# PWR.net
KiCad netlist of a schematic drawn in Altium Designer
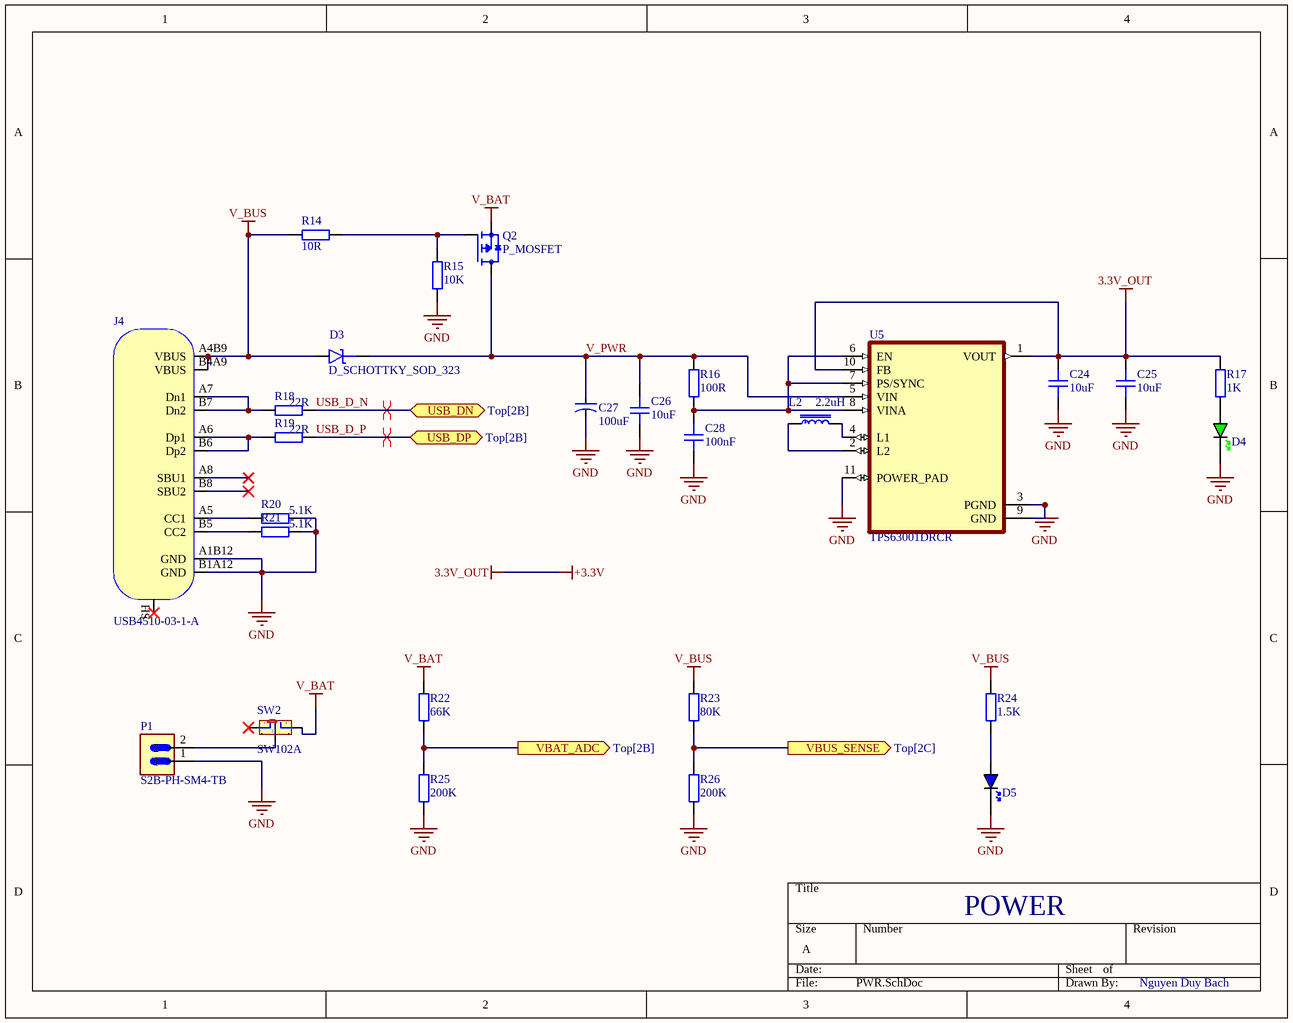
[diagram p0: PWR.SchDoc]

(export (version "E")
  (design (tool "Eeschema 10.0.6"))
  (components
    (comp (ref "C24")
      (value "10uF")
      (footprint "CAP_1206")
      (description "Capacitor SMD 1206")
      (libsource (lib "Project") (part "CAP_1206"))
    )
    (comp (ref "C25")
      (value "10uF")
      (footprint "CAP_1206")
      (description "Capacitor SMD 1206")
      (libsource (lib "Project") (part "CAP_1206"))
    )
    (comp (ref "C26")
      (value "10uF")
      (footprint "CAP_1206")
      (description "Capacitor SMD 1206")
      (libsource (lib "Project") (part "CAP_1206"))
    )
    (comp (ref "C27")
      (value "100uF")
      (footprint "CAP-ALU-SMD-6.3x7.7x2.2")
      (description "Polarized Capacitor (Axial)")
      (fields (field (name "PUBLISHER") "Altium Limited"))
      (libsource (lib "LIBRARY") (part "CN-ALU-SMD"))
    )
    (comp (ref "C28")
      (value "100nF")
      (footprint "CAP_0603")
      (description "Capacitor SMD 0603")
      (libsource (lib "Project") (part "CAP_0603"))
    )
    (comp (ref "D3")
      (value "D_SCHOTTKY_SOD_323")
      (footprint "SOD-323")
      (description "Diode Schottky SMD SOD-323")
      (libsource (lib "Schematic-Lib-PhilsLab") (part "D_SCHOTTKY_SOD_323"))
    )
    (comp (ref "D4")
      (value "GREEN")
      (footprint "LED_0805_GREEN")
      (description "LED 0805 GREEN SMD")
      (libsource (lib "Project") (part "LED_0805_GREEN"))
    )
    (comp (ref "D5")
      (value "BLUE")
      (footprint "LED_0805_BLUE")
      (description "LED 0805 BLUE SMD")
      (libsource (lib "Project") (part "LED_0805_BLUE"))
    )
    (comp (ref "J4")
      (value "USB4510-03-1-A")
      (footprint "USB4510-03-1-A")
      (description "USB Connector Type C SMT Mid-Mount 16 Pin")
      (fields (field (name "MANUFACTURER") "GCT"))
      (libsource (lib "Schematic-Lib-PhilsLab") (part "USB4510-03-1-A"))
    )
    (comp (ref "L2")
      (value "2.2uH")
      (footprint "INDC6060X300")
      (description "SMD Inductor 10uH-20%-5A")
      (fields (field (name "MF") "Codaca") (field (name "MP") "CSAB0630-100M"))
      (libsource (lib "Project") (part "CSAB0630-100M"))
    )
    (comp (ref "P1")
      (value "S2B-PH-SM4-TB")
      (footprint "JST_S2B-PH-SM4-TB")
      (description "Connector Header Surface Mount, Right Angle 2 position 0.079 (2.00mm)")
      (fields (field (name "MF") "JST Sales"))
      (libsource (lib "Project") (part "S2B-PH-SM4-TB"))
    )
    (comp (ref "Q2")
      (value "P_MOSFET")
      (footprint "P_MOSFET_SOT23")
      (description "MOSFET, SOT-23, P, -30V, -4A, 0.065â„¦, 150Â°C")
      (fields (field (name "MF") "Diotec Semiconductor") (field (name "MP") "MMFTP3401"))
      (libsource (lib "Project") (part "P_MOSFET"))
    )
    (comp (ref "R14")
      (value "10R")
      (footprint "RES_0603")
      (description "Resistor SMD 0603")
      (libsource (lib "Project") (part "RES_0603"))
    )
    (comp (ref "R15")
      (value "10K")
      (footprint "RES_0603")
      (description "Resistor SMD 0603")
      (libsource (lib "Project") (part "RES_0603"))
    )
    (comp (ref "R16")
      (value "100R")
      (footprint "RES_1206")
      (description "Resistor SMD 1206")
      (libsource (lib "Project") (part "RES_1206"))
    )
    (comp (ref "R17")
      (value "1K")
      (footprint "RES_0805")
      (description "Resistor SMD 0805")
      (libsource (lib "Project") (part "RES_0805"))
    )
    (comp (ref "R18")
      (value "22R")
      (footprint "RES_0603")
      (description "Resistor SMD 0603")
      (libsource (lib "Project") (part "RES_0603"))
    )
    (comp (ref "R19")
      (value "22R")
      (footprint "RES_0603")
      (description "Resistor SMD 0603")
      (libsource (lib "Project") (part "RES_0603"))
    )
    (comp (ref "R20")
      (value "5.1K")
      (footprint "RES_0603")
      (description "Resistor SMD 0603")
      (libsource (lib "Project") (part "RES_0603"))
    )
    (comp (ref "R21")
      (value "5.1K")
      (footprint "RES_0603")
      (description "Resistor SMD 0603")
      (libsource (lib "Project") (part "RES_0603"))
    )
    (comp (ref "R22")
      (value "66K")
      (footprint "RES_0603")
      (description "Resistor SMD 0603")
      (libsource (lib "Project") (part "RES_0603"))
    )
    (comp (ref "R23")
      (value "80K")
      (footprint "RES_0603")
      (description "Resistor SMD 0603")
      (libsource (lib "Project") (part "RES_0603"))
    )
    (comp (ref "R24")
      (value "1.5K")
      (footprint "RES_0805")
      (description "Resistor SMD 0805")
      (libsource (lib "Project") (part "RES_0805"))
    )
    (comp (ref "R25")
      (value "200K")
      (footprint "RES_0603")
      (description "Resistor SMD 0603")
      (libsource (lib "Project") (part "RES_0603"))
    )
    (comp (ref "R26")
      (value "200K")
      (footprint "RES_0603")
      (description "Resistor SMD 0603")
      (libsource (lib "Project") (part "RES_0603"))
    )
    (comp (ref "SW2")
      (value "SW102A")
      (footprint "SW102")
      (description "Switch 102 on Broad")
      (libsource (lib "syhaunguyen") (part "SW102A"))
    )
    (comp (ref "U5")
      (value "TPS63001DRCR")
      (footprint "VREG_V62/16624-01YE")
      (description "96% Buck-Boost Converter with 1.7A Current Switches, 3.3V fixed Output voltage in 3x3 QFN")
      (fields (field (name "MF") "Texas Instruments"))
      (libsource (lib "Project") (part "TPS63001DRCR"))
    )
  )
  (nets
    (net (code "1") (name "+3.3V") (class "Default")
      (node (ref "C24") (pin "2") (pinfunction "2_2") (pintype "passive"))
      (node (ref "C25") (pin "2") (pinfunction "2_2") (pintype "passive"))
      (node (ref "R17") (pin "2") (pinfunction "2_2") (pintype "passive"))
      (node (ref "U5") (pin "1") (pinfunction "VOUT_1") (pintype "output"))
      (node (ref "U5") (pin "10") (pinfunction "FB_10") (pintype "input"))
    )
    (net (code "2") (name "/USB_D_N") (class "Default")
      (node (ref "R18") (pin "1") (pinfunction "1_1") (pintype "passive"))
    )
    (net (code "3") (name "/USB_D_P") (class "Default")
      (node (ref "R19") (pin "1") (pinfunction "1_1") (pintype "passive"))
    )
    (net (code "4") (name "/VBAT_ADC") (class "Default")
      (node (ref "R22") (pin "1") (pinfunction "1_1") (pintype "passive"))
      (node (ref "R25") (pin "2") (pinfunction "2_2") (pintype "passive"))
    )
    (net (code "5") (name "/VBUS_SENSE") (class "Default")
      (node (ref "R23") (pin "1") (pinfunction "1_1") (pintype "passive"))
      (node (ref "R26") (pin "2") (pinfunction "2_2") (pintype "passive"))
    )
    (net (code "6") (name "/V_PWR") (class "Default")
      (node (ref "C26") (pin "2") (pinfunction "2_2") (pintype "passive"))
      (node (ref "C27") (pin "1") (pinfunction "1_1") (pintype "passive"))
      (node (ref "D3") (pin "K") (pinfunction "K_K") (pintype "passive"))
      (node (ref "Q2") (pin "3") (pinfunction "D_3") (pintype "passive"))
      (node (ref "R16") (pin "2") (pinfunction "2_2") (pintype "passive"))
      (node (ref "U5") (pin "5") (pinfunction "VIN_5") (pintype "input"))
    )
    (net (code "7") (name "GND") (class "Default")
      (node (ref "C24") (pin "1") (pinfunction "1_1") (pintype "passive"))
      (node (ref "C25") (pin "1") (pinfunction "1_1") (pintype "passive"))
      (node (ref "C26") (pin "1") (pinfunction "1_1") (pintype "passive"))
      (node (ref "C27") (pin "2") (pinfunction "2_2") (pintype "passive"))
      (node (ref "C28") (pin "1") (pinfunction "1_1") (pintype "passive"))
      (node (ref "D4") (pin "K") (pinfunction "K_K") (pintype "passive"))
      (node (ref "D5") (pin "K") (pinfunction "K_K") (pintype "passive"))
      (node (ref "J4") (pin "A1B12") (pinfunction "GND_A1B12") (pintype "passive"))
      (node (ref "J4") (pin "B1A12") (pinfunction "GND_B1A12") (pintype "passive"))
      (node (ref "P1") (pin "1") (pinfunction "1_1") (pintype "passive"))
      (node (ref "R15") (pin "1") (pinfunction "1_1") (pintype "passive"))
      (node (ref "R20") (pin "1") (pinfunction "1_1") (pintype "passive"))
      (node (ref "R21") (pin "1") (pinfunction "1_1") (pintype "passive"))
      (node (ref "R25") (pin "1") (pinfunction "1_1") (pintype "passive"))
      (node (ref "R26") (pin "1") (pinfunction "1_1") (pintype "passive"))
      (node (ref "U5") (pin "11") (pinfunction "POWER_PAD_11") (pintype "bidirectional"))
      (node (ref "U5") (pin "3") (pinfunction "PGND_3") (pintype "power_in"))
      (node (ref "U5") (pin "9") (pinfunction "GND_9") (pintype "power_in"))
    )
    (net (code "8") (name "Net-(D4-PadA)") (class "Default")
      (node (ref "D4") (pin "A") (pinfunction "A_A") (pintype "passive"))
      (node (ref "R17") (pin "1") (pinfunction "1_1") (pintype "passive"))
    )
    (net (code "9") (name "Net-(D5-PadA)") (class "Default")
      (node (ref "D5") (pin "A") (pinfunction "A_A") (pintype "passive"))
      (node (ref "R24") (pin "1") (pinfunction "1_1") (pintype "passive"))
    )
    (net (code "10") (name "Net-(J4-CC1)") (class "Default")
      (node (ref "J4") (pin "A5") (pinfunction "CC1_A5") (pintype "passive"))
      (node (ref "R20") (pin "2") (pinfunction "2_2") (pintype "passive"))
    )
    (net (code "11") (name "Net-(J4-CC2)") (class "Default")
      (node (ref "J4") (pin "B5") (pinfunction "CC2_B5") (pintype "passive"))
      (node (ref "R21") (pin "2") (pinfunction "2_2") (pintype "passive"))
    )
    (net (code "12") (name "Net-(J4-Dn1)") (class "Default")
      (node (ref "J4") (pin "A7") (pinfunction "Dn1_A7") (pintype "passive"))
      (node (ref "J4") (pin "B7") (pinfunction "Dn2_B7") (pintype "passive"))
      (node (ref "R18") (pin "2") (pinfunction "2_2") (pintype "passive"))
    )
    (net (code "13") (name "Net-(J4-Dp1)") (class "Default")
      (node (ref "J4") (pin "A6") (pinfunction "Dp1_A6") (pintype "passive"))
      (node (ref "J4") (pin "B6") (pinfunction "Dp2_B6") (pintype "passive"))
      (node (ref "R19") (pin "2") (pinfunction "2_2") (pintype "passive"))
    )
    (net (code "14") (name "Net-(P1-Pad2)") (class "Default")
      (node (ref "P1") (pin "2") (pinfunction "2_2") (pintype "passive"))
      (node (ref "SW2") (pin "2") (pinfunction "2_2") (pintype "passive"))
    )
    (net (code "15") (name "Net-(Q2-G)") (class "Default")
      (node (ref "Q2") (pin "1") (pinfunction "G_1") (pintype "passive"))
      (node (ref "R14") (pin "1") (pinfunction "1_1") (pintype "passive"))
      (node (ref "R15") (pin "2") (pinfunction "2_2") (pintype "passive"))
    )
    (net (code "16") (name "Net-(U5-EN)") (class "Default")
      (node (ref "C28") (pin "2") (pinfunction "2_2") (pintype "passive"))
      (node (ref "R16") (pin "1") (pinfunction "1_1") (pintype "passive"))
      (node (ref "U5") (pin "6") (pinfunction "EN_6") (pintype "input"))
      (node (ref "U5") (pin "7") (pinfunction "PS/SYNC_7") (pintype "input"))
      (node (ref "U5") (pin "8") (pinfunction "VINA_8") (pintype "input"))
    )
    (net (code "17") (name "Net-(U5-L1)") (class "Default")
      (node (ref "L2") (pin "2") (pinfunction "2_2") (pintype "passive"))
      (node (ref "U5") (pin "4") (pinfunction "L1_4") (pintype "bidirectional"))
    )
    (net (code "18") (name "Net-(U5-L2)") (class "Default")
      (node (ref "L2") (pin "1") (pinfunction "1_1") (pintype "passive"))
      (node (ref "U5") (pin "2") (pinfunction "L2_2") (pintype "bidirectional"))
    )
    (net (code "19") (name "V_BAT") (class "Default")
      (node (ref "Q2") (pin "2") (pinfunction "S_2") (pintype "passive"))
      (node (ref "R22") (pin "2") (pinfunction "2_2") (pintype "passive"))
      (node (ref "SW2") (pin "3") (pinfunction "3_3") (pintype "passive"))
    )
    (net (code "20") (name "V_BUS") (class "Default")
      (node (ref "D3") (pin "A") (pinfunction "A_A") (pintype "passive"))
      (node (ref "J4") (pin "A4B9") (pinfunction "VBUS_A4B9") (pintype "passive"))
      (node (ref "J4") (pin "B4A9") (pinfunction "VBUS_B4A9") (pintype "passive"))
      (node (ref "R14") (pin "2") (pinfunction "2_2") (pintype "passive"))
      (node (ref "R23") (pin "2") (pinfunction "2_2") (pintype "passive"))
      (node (ref "R24") (pin "2") (pinfunction "2_2") (pintype "passive"))
    )
    (net (code "21") (name "unconnected-(J4-SBU1-PadA8)") (class "Default")
      (node (ref "J4") (pin "A8") (pinfunction "SBU1_A8") (pintype "passive+no_connect"))
    )
    (net (code "22") (name "unconnected-(J4-SBU2-PadB8)") (class "Default")
      (node (ref "J4") (pin "B8") (pinfunction "SBU2_B8") (pintype "passive+no_connect"))
    )
    (net (code "23") (name "unconnected-(J4-SHIELD-PadSH)") (class "Default")
      (node (ref "J4") (pin "SH") (pinfunction "SHIELD_SH") (pintype "passive+no_connect"))
    )
    (net (code "24") (name "unconnected-(SW2-Pad1)") (class "Default")
      (node (ref "SW2") (pin "1") (pinfunction "1_1") (pintype "passive+no_connect"))
    )
    (net (code "25") (name "unconnected-(SW2-Pad4)") (class "Default")
      (node (ref "SW2") (pin "4") (pinfunction "4_4") (pintype "passive"))
    )
    (net (code "26") (name "unconnected-(SW2-Pad5)") (class "Default")
      (node (ref "SW2") (pin "5") (pinfunction "5_5") (pintype "passive"))
    )
  )
)
